# gd32foc.net
KiCad netlist of a schematic drawn in Altium Designer
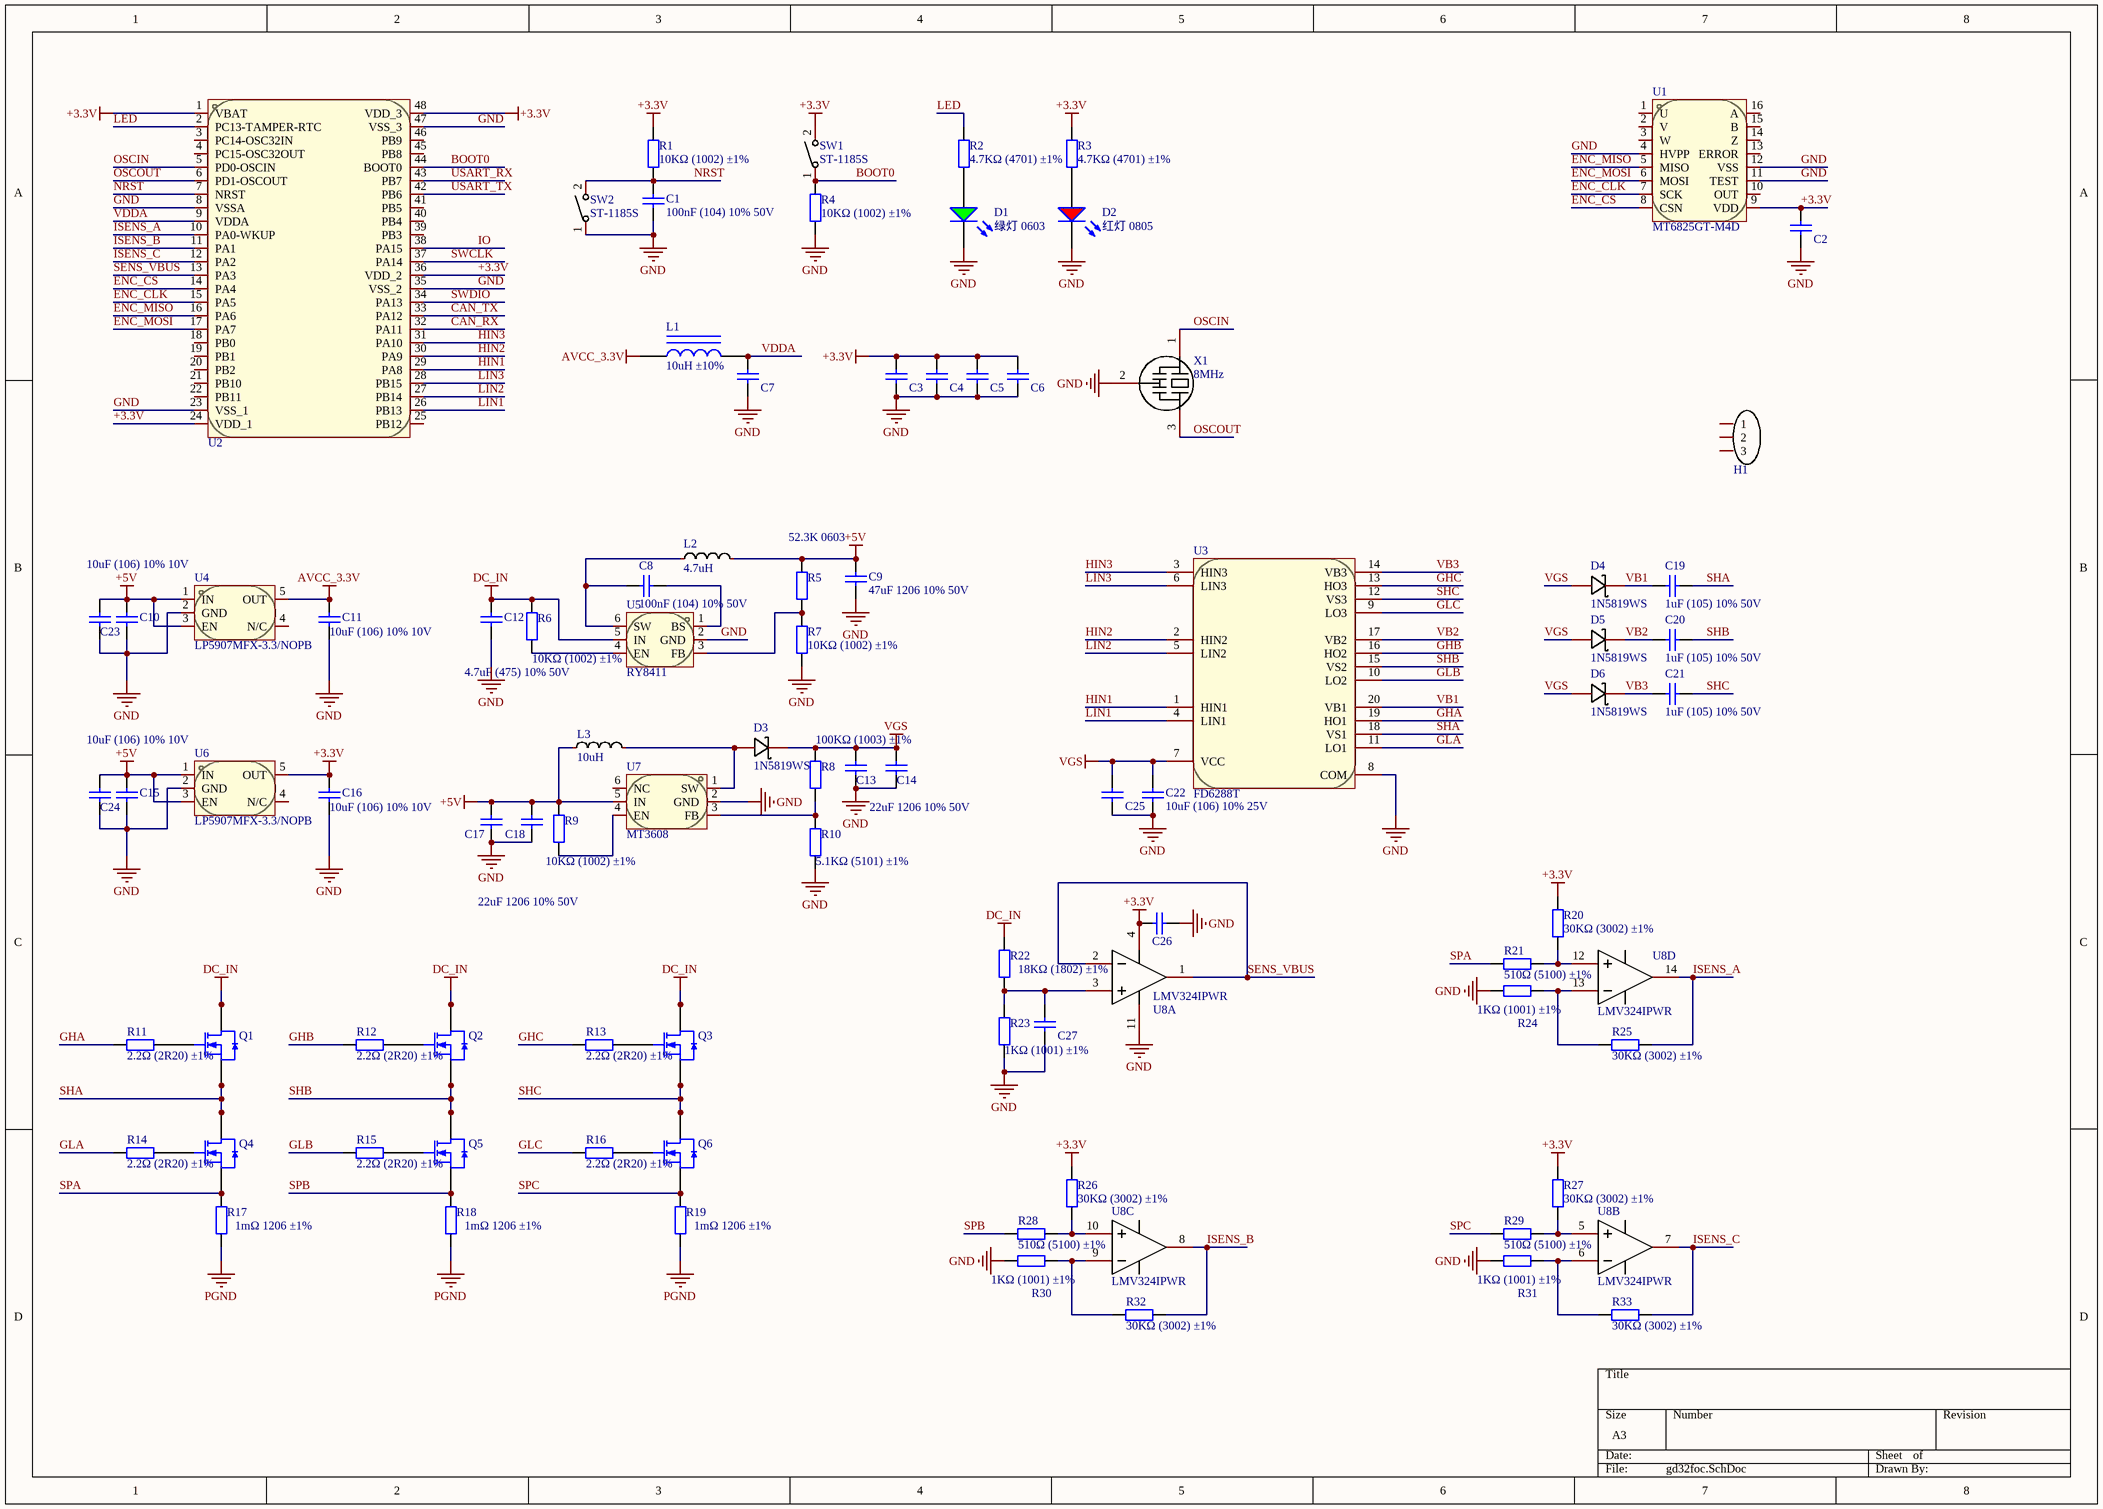
[diagram p0: gd32foc.SchDoc]

(export (version "E")
  (design (tool "Eeschema 10.0.6"))
  (components
    (comp (ref "C1")
      (value "100nF (104) 10% 50V")
      (footprint "0603_C")
      (description "贴片电容")
      (libsource (lib "Miscellaneous Devices LC") (part "0603 100nF (104) 10% 50V"))
    )
    (comp (ref "C2")
      (value "100nF (104) 10% 50V")
      (footprint "0603_C")
      (description "贴片电容")
      (libsource (lib "Miscellaneous Devices LC") (part "0603 100nF (104) 10% 50V"))
    )
    (comp (ref "C3")
      (value "100nF (104) 10% 50V")
      (footprint "0603_C")
      (description "贴片电容")
      (libsource (lib "Miscellaneous Devices LC") (part "0603 100nF (104) 10% 50V"))
    )
    (comp (ref "C4")
      (value "100nF (104) 10% 50V")
      (footprint "0603_C")
      (description "贴片电容")
      (libsource (lib "Miscellaneous Devices LC") (part "0603 100nF (104) 10% 50V"))
    )
    (comp (ref "C5")
      (value "100nF (104) 10% 50V")
      (footprint "0603_C")
      (description "贴片电容")
      (libsource (lib "Miscellaneous Devices LC") (part "0603 100nF (104) 10% 50V"))
    )
    (comp (ref "C6")
      (value "100nF (104) 10% 50V")
      (footprint "0603_C")
      (description "贴片电容")
      (libsource (lib "Miscellaneous Devices LC") (part "0603 100nF (104) 10% 50V"))
    )
    (comp (ref "C7")
      (value "100nF (104) 10% 50V")
      (footprint "0603_C")
      (description "贴片电容")
      (libsource (lib "Miscellaneous Devices LC") (part "0603 100nF (104) 10% 50V"))
    )
    (comp (ref "C8")
      (value "100nF (104) 10% 50V")
      (footprint "0603_C")
      (description "贴片电容")
      (libsource (lib "Miscellaneous Devices LC") (part "0603 100nF (104) 10% 50V"))
    )
    (comp (ref "C9")
      (value "47uF 1206 10% 50V")
      (footprint "1206_C")
      (description "贴片电容")
      (libsource (lib "Miscellaneous Devices LC") (part "1206 4.7uF (475) 10% 50V"))
    )
    (comp (ref "C10")
      (value "10uF (106) 10% 10V")
      (footprint "0603_C")
      (description "贴片电容")
      (libsource (lib "Miscellaneous Devices LC") (part "0603 10uF (106) 10% 10V"))
    )
    (comp (ref "C11")
      (value "10uF (106) 10% 10V")
      (footprint "0603_C")
      (description "贴片电容")
      (libsource (lib "Miscellaneous Devices LC") (part "0603 10uF (106) 10% 10V"))
    )
    (comp (ref "C12")
      (value "4.7uF (475) 10% 50V")
      (footprint "1206_C")
      (description "贴片电容")
      (libsource (lib "Miscellaneous Devices LC") (part "1206 4.7uF (475) 10% 50V"))
    )
    (comp (ref "C13")
      (value "22uF 1206 10% 50V")
      (footprint "1206_C")
      (description "贴片电容")
      (libsource (lib "Miscellaneous Devices LC") (part "1206 4.7uF (475) 10% 50V"))
    )
    (comp (ref "C14")
      (value "100nF (104) 10% 50V")
      (footprint "0603_C")
      (description "贴片电容")
      (libsource (lib "Miscellaneous Devices LC") (part "0603 100nF (104) 10% 50V"))
    )
    (comp (ref "C15")
      (value "10uF (106) 10% 10V")
      (footprint "0603_C")
      (description "贴片电容")
      (libsource (lib "Miscellaneous Devices LC") (part "0603 10uF (106) 10% 10V"))
    )
    (comp (ref "C16")
      (value "10uF (106) 10% 10V")
      (footprint "0603_C")
      (description "贴片电容")
      (libsource (lib "Miscellaneous Devices LC") (part "0603 10uF (106) 10% 10V"))
    )
    (comp (ref "C17")
      (value "22uF 1206 10% 50V")
      (footprint "1206_C")
      (description "贴片电容")
      (libsource (lib "Miscellaneous Devices LC") (part "1206 4.7uF (475) 10% 50V"))
    )
    (comp (ref "C18")
      (value "100nF (104) 10% 50V")
      (footprint "0603_C")
      (description "贴片电容")
      (libsource (lib "Miscellaneous Devices LC") (part "0603 100nF (104) 10% 50V"))
    )
    (comp (ref "C19")
      (value "1uF (105) 10% 50V")
      (footprint "0603_C")
      (description "贴片电容")
      (libsource (lib "Miscellaneous Devices LC") (part "0603 1uF (105) 10% 50V"))
    )
    (comp (ref "C20")
      (value "1uF (105) 10% 50V")
      (footprint "0603_C")
      (description "贴片电容")
      (libsource (lib "Miscellaneous Devices LC") (part "0603 1uF (105) 10% 50V"))
    )
    (comp (ref "C21")
      (value "1uF (105) 10% 50V")
      (footprint "0603_C")
      (description "贴片电容")
      (libsource (lib "Miscellaneous Devices LC") (part "0603 1uF (105) 10% 50V"))
    )
    (comp (ref "C22")
      (value "10uF (106) 10% 25V")
      (footprint "0805_C")
      (description "贴片电容")
      (libsource (lib "Miscellaneous Devices LC") (part "0805 10uF (106) 10% 25V"))
    )
    (comp (ref "C23")
      (value "100nF (104) 10% 50V")
      (footprint "0603_C")
      (description "贴片电容")
      (libsource (lib "Miscellaneous Devices LC") (part "0603 100nF (104) 10% 50V"))
    )
    (comp (ref "C24")
      (value "100nF (104) 10% 50V")
      (footprint "0603_C")
      (description "贴片电容")
      (libsource (lib "Miscellaneous Devices LC") (part "0603 100nF (104) 10% 50V"))
    )
    (comp (ref "C25")
      (value "100nF (104) 10% 50V")
      (footprint "0603_C")
      (description "贴片电容")
      (libsource (lib "Miscellaneous Devices LC") (part "0603 100nF (104) 10% 50V"))
    )
    (comp (ref "C26")
      (value "100nF (104) 10% 50V")
      (footprint "0603_C")
      (description "贴片电容")
      (libsource (lib "Miscellaneous Devices LC") (part "0603 100nF (104) 10% 50V"))
    )
    (comp (ref "C27")
      (value "100nF (104) 10% 50V")
      (footprint "0603_C")
      (description "贴片电容")
      (libsource (lib "Miscellaneous Devices LC") (part "0603 100nF (104) 10% 50V"))
    )
    (comp (ref "D1")
      (value "绿灯 0603")
      (footprint "0603_LED_S1")
      (description "发光二极管")
      (libsource (lib "Miscellaneous Devices LC") (part "0603 绿灯"))
    )
    (comp (ref "D2")
      (value "红灯 0805")
      (footprint "0805_LED_S1")
      (description "发光二极管")
      (libsource (lib "Miscellaneous Devices LC") (part "0805 红灯"))
    )
    (comp (ref "D3")
      (value "1N5819WS")
      (footprint "SOD-323_L1.8-W1.3-LS2.5-RD")
      (description "正向压降(Vf):600mV@1A;直流反向耐压(Vr):40V;平均整流电流(Io):1A;")
      (fields (field (name "MANUFACTURER") "Hottech(合科泰)") (field (name "NAME") "1N5819WS"))
      (libsource (lib "MyLib") (part "1N5819WS_C191023"))
    )
    (comp (ref "D4")
      (value "1N5819WS")
      (footprint "SOD-323_L1.8-W1.3-LS2.5-RD")
      (description "正向压降(Vf):600mV@1A;直流反向耐压(Vr):40V;平均整流电流(Io):1A;")
      (fields (field (name "MANUFACTURER") "Hottech(合科泰)") (field (name "NAME") "1N5819WS"))
      (libsource (lib "MyLib") (part "1N5819WS_C191023"))
    )
    (comp (ref "D5")
      (value "1N5819WS")
      (footprint "SOD-323_L1.8-W1.3-LS2.5-RD")
      (description "正向压降(Vf):600mV@1A;直流反向耐压(Vr):40V;平均整流电流(Io):1A;")
      (fields (field (name "MANUFACTURER") "Hottech(合科泰)") (field (name "NAME") "1N5819WS"))
      (libsource (lib "MyLib") (part "1N5819WS_C191023"))
    )
    (comp (ref "D6")
      (value "1N5819WS")
      (footprint "SOD-323_L1.8-W1.3-LS2.5-RD")
      (description "正向压降(Vf):600mV@1A;直流反向耐压(Vr):40V;平均整流电流(Io):1A;")
      (fields (field (name "MANUFACTURER") "Hottech(合科泰)") (field (name "NAME") "1N5819WS"))
      (libsource (lib "MyLib") (part "1N5819WS_C191023"))
    )
    (comp (ref "H1") (value "MR30-M") (footprint "MR30-M") (libsource (lib "MyLib") (part "MR30-M_卧")))
    (comp (ref "L1")
      (value "10uH ±10%")
      (footprint "0603_L")
      (description "贴片电感")
      (libsource (lib "Miscellaneous Devices LC") (part "0603 10uH 10%"))
    )
    (comp (ref "L2")
      (value "4.7uH")
      (footprint "IND-SMD_L2.5-W2.0")
      (description "电感值:4.7uH;精度:±20%;额定电流:840mA;类型:-;饱和电流(Isat):1.25A;")
      (fields
        (field (name "MANUFACTURER") "Sunlord(顺络)")
        (field (name "MANUFACTURER PART") "SWPA252012S4R7MT")
        (field (name "NAME") "4.7uH")
      )
      (libsource (lib "MyLib") (part "SWPA252012S4R7MT"))
    )
    (comp (ref "L3")
      (value "10uH")
      (footprint "IND-SMD_L2.5-W2.0_WPN252012H")
      (description "电感值:10uH;精度:±20%;额定电流:850mA;直流电阻(DCR):480mΩ;")
      (fields
        (field (name "MANUFACTURER") "Sunlord(顺络)")
        (field (name "MANUFACTURER PART") "WPN252012H100MT")
        (field (name "NAME") "10uH")
      )
      (libsource (lib "MyLib") (part "WPN252012H100MT"))
    )
    (comp (ref "Q1")
      (value "HYG025N06LS1C2")
      (footprint "DFN-8_L5.9-W5.2-P1.27-LS6.2-BL")
      (fields (field (name "MANUFACTURER") "HUAYI(华羿微)"))
      (libsource (lib "MyLib") (part "HYG025N06LS1C2"))
    )
    (comp (ref "Q2")
      (value "HYG025N06LS1C2")
      (footprint "DFN-8_L5.9-W5.2-P1.27-LS6.2-BL")
      (fields (field (name "MANUFACTURER") "HUAYI(华羿微)"))
      (libsource (lib "MyLib") (part "HYG025N06LS1C2"))
    )
    (comp (ref "Q3")
      (value "HYG025N06LS1C2")
      (footprint "DFN-8_L5.9-W5.2-P1.27-LS6.2-BL")
      (fields (field (name "MANUFACTURER") "HUAYI(华羿微)"))
      (libsource (lib "MyLib") (part "HYG025N06LS1C2"))
    )
    (comp (ref "Q4")
      (value "HYG025N06LS1C2")
      (footprint "DFN-8_L5.9-W5.2-P1.27-LS6.2-BL")
      (fields (field (name "MANUFACTURER") "HUAYI(华羿微)"))
      (libsource (lib "MyLib") (part "HYG025N06LS1C2"))
    )
    (comp (ref "Q5")
      (value "HYG025N06LS1C2")
      (footprint "DFN-8_L5.9-W5.2-P1.27-LS6.2-BL")
      (fields (field (name "MANUFACTURER") "HUAYI(华羿微)"))
      (libsource (lib "MyLib") (part "HYG025N06LS1C2"))
    )
    (comp (ref "Q6")
      (value "HYG025N06LS1C2")
      (footprint "DFN-8_L5.9-W5.2-P1.27-LS6.2-BL")
      (fields (field (name "MANUFACTURER") "HUAYI(华羿微)"))
      (libsource (lib "MyLib") (part "HYG025N06LS1C2"))
    )
    (comp (ref "R1")
      (value "10KΩ (1002) ±1%")
      (footprint "0603_R")
      (description "贴片电阻")
      (libsource (lib "Miscellaneous Devices LC") (part "0603 10KΩ (1002) 1%"))
    )
    (comp (ref "R2")
      (value "4.7KΩ (4701) ±1%")
      (footprint "0603_R")
      (description "贴片电阻")
      (libsource (lib "Miscellaneous Devices LC") (part "0603 4.7KΩ (4701) 1%"))
    )
    (comp (ref "R3")
      (value "4.7KΩ (4701) ±1%")
      (footprint "0603_R")
      (description "贴片电阻")
      (libsource (lib "Miscellaneous Devices LC") (part "0603 4.7KΩ (4701) 1%"))
    )
    (comp (ref "R4")
      (value "10KΩ (1002) ±1%")
      (footprint "0603_R")
      (description "贴片电阻")
      (libsource (lib "Miscellaneous Devices LC") (part "0603 10KΩ (1002) 1%"))
    )
    (comp (ref "R5")
      (value "52.3K 0603")
      (footprint "0603_R")
      (description "贴片电阻")
      (libsource (lib "Miscellaneous Devices LC") (part "0603 100KΩ (1003) 1%"))
    )
    (comp (ref "R6")
      (value "10KΩ (1002) ±1%")
      (footprint "0603_R")
      (description "贴片电阻")
      (libsource (lib "Miscellaneous Devices LC") (part "0603 10KΩ (1002) 1%"))
    )
    (comp (ref "R7")
      (value "10KΩ (1002) ±1%")
      (footprint "0603_R")
      (description "贴片电阻")
      (libsource (lib "Miscellaneous Devices LC") (part "0603 10KΩ (1002) 1%"))
    )
    (comp (ref "R8")
      (value "100KΩ (1003) ±1%")
      (footprint "0603_R")
      (description "贴片电阻")
      (libsource (lib "Miscellaneous Devices LC") (part "0603 100KΩ (1003) 1%"))
    )
    (comp (ref "R9")
      (value "10KΩ (1002) ±1%")
      (footprint "0603_R")
      (description "贴片电阻")
      (libsource (lib "Miscellaneous Devices LC") (part "0603 10KΩ (1002) 1%"))
    )
    (comp (ref "R10")
      (value "5.1KΩ (5101) ±1%")
      (footprint "0603_R")
      (description "贴片电阻")
      (libsource (lib "Miscellaneous Devices LC") (part "0603 5.1KΩ (5101) 1%"))
    )
    (comp (ref "R11")
      (value "2.2Ω (2R20) ±1%")
      (footprint "0603_R")
      (description "贴片电阻")
      (libsource (lib "Miscellaneous Devices LC") (part "0603 2.2Ω (2R20) 1%"))
    )
    (comp (ref "R12")
      (value "2.2Ω (2R20) ±1%")
      (footprint "0603_R")
      (description "贴片电阻")
      (libsource (lib "Miscellaneous Devices LC") (part "0603 2.2Ω (2R20) 1%"))
    )
    (comp (ref "R13")
      (value "2.2Ω (2R20) ±1%")
      (footprint "0603_R")
      (description "贴片电阻")
      (libsource (lib "Miscellaneous Devices LC") (part "0603 2.2Ω (2R20) 1%"))
    )
    (comp (ref "R14")
      (value "2.2Ω (2R20) ±1%")
      (footprint "0603_R")
      (description "贴片电阻")
      (libsource (lib "Miscellaneous Devices LC") (part "0603 2.2Ω (2R20) 1%"))
    )
    (comp (ref "R15")
      (value "2.2Ω (2R20) ±1%")
      (footprint "0603_R")
      (description "贴片电阻")
      (libsource (lib "Miscellaneous Devices LC") (part "0603 2.2Ω (2R20) 1%"))
    )
    (comp (ref "R16")
      (value "2.2Ω (2R20) ±1%")
      (footprint "0603_R")
      (description "贴片电阻")
      (libsource (lib "Miscellaneous Devices LC") (part "0603 2.2Ω (2R20) 1%"))
    )
    (comp (ref "R17")
      (value "1mΩ 1206 ±1%")
      (footprint "1206_R")
      (description "贴片电阻")
      (libsource (lib "Miscellaneous Devices LC") (part "1206 0.1Ω (R100) 1%"))
    )
    (comp (ref "R18")
      (value "1mΩ 1206 ±1%")
      (footprint "1206_R")
      (description "贴片电阻")
      (libsource (lib "Miscellaneous Devices LC") (part "1206 0.1Ω (R100) 1%"))
    )
    (comp (ref "R19")
      (value "1mΩ 1206 ±1%")
      (footprint "1206_R")
      (description "贴片电阻")
      (libsource (lib "Miscellaneous Devices LC") (part "1206 0.1Ω (R100) 1%"))
    )
    (comp (ref "R20")
      (value "30KΩ (3002) ±1%")
      (footprint "0603_R")
      (description "贴片电阻")
      (libsource (lib "") (part "0603 30KΩ (3002) 1%_1"))
    )
    (comp (ref "R21")
      (value "510Ω (5100) ±1%")
      (footprint "0603_R")
      (description "贴片电阻")
      (libsource (lib "Miscellaneous Devices LC") (part "0603 510Ω (5100) 1%"))
    )
    (comp (ref "R22")
      (value "18KΩ (1802) ±1%")
      (footprint "0603_R")
      (description "贴片电阻")
      (libsource (lib "Miscellaneous Devices LC") (part "0603 18KΩ (1802) 1%"))
    )
    (comp (ref "R23")
      (value "1KΩ (1001) ±1%")
      (footprint "0603_R")
      (description "贴片电阻")
      (libsource (lib "") (part "0603 1KΩ (1001) 1%_1"))
    )
    (comp (ref "R24")
      (value "1KΩ (1001) ±1%")
      (footprint "0603_R")
      (description "贴片电阻")
      (libsource (lib "Miscellaneous Devices LC") (part "0603 1KΩ (1001) 1%"))
    )
    (comp (ref "R25")
      (value "30KΩ (3002) ±1%")
      (footprint "0603_R")
      (description "贴片电阻")
      (libsource (lib "Miscellaneous Devices LC") (part "0603 30KΩ (3002) 1%"))
    )
    (comp (ref "R26")
      (value "30KΩ (3002) ±1%")
      (footprint "0603_R")
      (description "贴片电阻")
      (libsource (lib "") (part "0603 30KΩ (3002) 1%_1"))
    )
    (comp (ref "R27")
      (value "30KΩ (3002) ±1%")
      (footprint "0603_R")
      (description "贴片电阻")
      (libsource (lib "") (part "0603 30KΩ (3002) 1%_1"))
    )
    (comp (ref "R28")
      (value "510Ω (5100) ±1%")
      (footprint "0603_R")
      (description "贴片电阻")
      (libsource (lib "Miscellaneous Devices LC") (part "0603 510Ω (5100) 1%"))
    )
    (comp (ref "R29")
      (value "510Ω (5100) ±1%")
      (footprint "0603_R")
      (description "贴片电阻")
      (libsource (lib "Miscellaneous Devices LC") (part "0603 510Ω (5100) 1%"))
    )
    (comp (ref "R30")
      (value "1KΩ (1001) ±1%")
      (footprint "0603_R")
      (description "贴片电阻")
      (libsource (lib "Miscellaneous Devices LC") (part "0603 1KΩ (1001) 1%"))
    )
    (comp (ref "R31")
      (value "1KΩ (1001) ±1%")
      (footprint "0603_R")
      (description "贴片电阻")
      (libsource (lib "Miscellaneous Devices LC") (part "0603 1KΩ (1001) 1%"))
    )
    (comp (ref "R32")
      (value "30KΩ (3002) ±1%")
      (footprint "0603_R")
      (description "贴片电阻")
      (libsource (lib "Miscellaneous Devices LC") (part "0603 30KΩ (3002) 1%"))
    )
    (comp (ref "R33")
      (value "30KΩ (3002) ±1%")
      (footprint "0603_R")
      (description "贴片电阻")
      (libsource (lib "Miscellaneous Devices LC") (part "0603 30KΩ (3002) 1%"))
    )
    (comp (ref "SW1")
      (value "ST-1185S")
      (footprint "SW-SMD_ST-1185S")
      (description "电路结构:单刀单掷;带支架:否;触点电流:50mA;额定电压(DC):12V;安装方式:立贴;绝缘电阻:100MΩ;机械寿命:10万次;")
      (fields (field (name "MANUFACTURER") "RISHENG(日昇)") (field (name "NAME") "ST-1185S"))
      (libsource (lib "MyLib") (part "ST-1185S"))
    )
    (comp (ref "SW2")
      (value "ST-1185S")
      (footprint "SW-SMD_ST-1185S")
      (description "电路结构:单刀单掷;带支架:否;触点电流:50mA;额定电压(DC):12V;安装方式:立贴;绝缘电阻:100MΩ;机械寿命:10万次;")
      (fields (field (name "MANUFACTURER") "RISHENG(日昇)") (field (name "NAME") "ST-1185S"))
      (libsource (lib "MyLib") (part "ST-1185S"))
    )
    (comp (ref "U1")
      (value "MT6825GT-M4D")
      (footprint "TSSOP-16_L5.0-W4.4-P0.65-LS6.4-BL")
      (description "AB=2500线，Z=4LSB, UVW=4对极, PWM=1KHz，四线SPI")
      (fields (field (name "MANUFACTURER") "MagnTek(麦歌恩)") (field (name "NAME") "MT6825GT-M4D"))
      (libsource (lib "MyLib") (part "MT6825GT-M4D"))
    )
    (comp (ref "U2")
      (value "GD32C103CBT6")
      (footprint "LQFP-48_L7.0-W7.0-P0.50-LS9.0-BL")
      (description "CPU内核:ARM Cortex-M4;CPU最大主频:120MHz;程序存储容量:128KB;程序存储器类型:FLASH;GPIO端口数量:37;工作电压范围:-;RAM总容量:32KB;")
      (fields (field (name "MANUFACTURER") "GigaDevice(兆易创新)"))
      (libsource (lib "MyLib") (part "GD32C103CBT6"))
    )
    (comp (ref "U3")
      (value "FD6288T")
      (footprint "TSSOP-20_L6.5-W4.4-P0.65-LS6.4-BL")
      (description "三个独立的半桥栅极驱动集成电路芯片")
      (fields (field (name "MANUFACTURER") "Fortior Tech(峰岹)") (field (name "NAME") "FD6288T"))
      (libsource (lib "MyLib") (part "FD6288T"))
    )
    (comp (ref "U4")
      (value "LP5907MFX-3.3/NOPB")
      (footprint "SOT-23-5_L3.0-W1.7-P0.95-LS2.8-BR")
      (description "输出类型:固定;输出极性:正;最大输入电压:5.5V;输出电压:3.3V;输出电流:250mA;电源纹波抑制比(PSRR):90dB;")
      (fields (field (name "MANUFACTURER") "TI(德州仪器)") (field (name "NAME") "LP5907MFX-3.3/NOPB"))
      (libsource (lib "MyLib") (part "LP5907MFX-3.3/NOPB"))
    )
    (comp (ref "U5")
      (value "RY8411")
      (footprint "SOT-23-6_L2.9-W1.6-P0.95-LS2.8-TL")
      (fields (field (name "MANUFACTURER") "RYCHiP(蕊源)") (field (name "NAME") "RY8411"))
      (libsource (lib "MyLib") (part "RY8411_C2935411"))
    )
    (comp (ref "U6")
      (value "LP5907MFX-3.3/NOPB")
      (footprint "SOT-23-5_L3.0-W1.7-P0.95-LS2.8-BR")
      (description "输出类型:固定;输出极性:正;最大输入电压:5.5V;输出电压:3.3V;输出电流:250mA;电源纹波抑制比(PSRR):90dB;")
      (fields (field (name "MANUFACTURER") "TI(德州仪器)") (field (name "NAME") "LP5907MFX-3.3/NOPB"))
      (libsource (lib "MyLib") (part "LP5907MFX-3.3/NOPB"))
    )
    (comp (ref "U7")
      (value "MT3608")
      (footprint "SOT-23-6_L2.9-W1.6-P0.95-LS2.8-BL")
      (description "功能类型:升压型;输入电压:2V~24V;输出电压:28V;输出电流(最大值):-;")
      (fields (field (name "MANUFACTURER") "西安航天民芯") (field (name "NAME") "MT3608"))
      (libsource (lib "MyLib") (part "MT3608"))
    )
    (comp (ref "U8")
      (value "LMV324IPWR")
      (footprint "TSSOP-14_L5.0-W4.4-P0.65-LS6.4-BL")
      (description "放大器组数:-;")
      (fields (field (name "MANUFACTURER") "TI(德州仪器)") (field (name "NAME") "LMV324IPWR"))
      (libsource (lib "MyLib") (part "LMV324IPWR"))
    )
    (comp (ref "X1")
      (value "8MHz")
      (footprint "OSC-SMD_3P-L3.2-W1.3-P1.2-L")
      (description "频率:8MHz;频率公差:±0.5%;内置负载电容:33pF;谐振阻抗:-;")
      (fields
        (field (name "MANUFACTURER") "muRata(村田)")
        (field (name "MANUFACTURER PART") "CSTCE8M00G55-R0")
        (field (name "NAME") "8MHz")
      )
      (libsource (lib "MyLib") (part "CSTCE8M00G55-R0"))
    )
  )
  (nets
    (net (code "1") (name "+3.3V") (class "Default")
      (node (ref "C16") (pin "2") (pinfunction "2_2") (pintype "passive"))
      (node (ref "C2") (pin "2") (pinfunction "2_2") (pintype "passive"))
      (node (ref "C26") (pin "2") (pinfunction "2_2") (pintype "passive"))
      (node (ref "C3") (pin "2") (pinfunction "2_2") (pintype "passive"))
      (node (ref "C4") (pin "2") (pinfunction "2_2") (pintype "passive"))
      (node (ref "C5") (pin "2") (pinfunction "2_2") (pintype "passive"))
      (node (ref "C6") (pin "2") (pinfunction "2_2") (pintype "passive"))
      (node (ref "R1") (pin "2") (pinfunction "2_2") (pintype "passive"))
      (node (ref "R20") (pin "2") (pinfunction "2_2") (pintype "passive"))
      (node (ref "R26") (pin "2") (pinfunction "2_2") (pintype "passive"))
      (node (ref "R27") (pin "2") (pinfunction "2_2") (pintype "passive"))
      (node (ref "R3") (pin "2") (pinfunction "2_2") (pintype "passive"))
      (node (ref "SW1") (pin "2") (pinfunction "2_2") (pintype "passive"))
      (node (ref "U1") (pin "9") (pinfunction "VDD_9") (pintype "passive"))
      (node (ref "U2") (pin "1") (pinfunction "VBAT_1") (pintype "passive"))
      (node (ref "U2") (pin "24") (pinfunction "VDD_1_24") (pintype "passive"))
      (node (ref "U2") (pin "36") (pinfunction "VDD_2_36") (pintype "passive"))
      (node (ref "U2") (pin "48") (pinfunction "VDD_3_48") (pintype "passive"))
      (node (ref "U6") (pin "5") (pinfunction "OUT_5") (pintype "passive"))
      (node (ref "U8") (pin "4") (pinfunction "VCC+_4") (pintype "passive"))
    )
    (net (code "2") (name "+5V") (class "Default")
      (node (ref "C10") (pin "2") (pinfunction "2_2") (pintype "passive"))
      (node (ref "C15") (pin "2") (pinfunction "2_2") (pintype "passive"))
      (node (ref "C17") (pin "2") (pinfunction "2_2") (pintype "passive"))
      (node (ref "C18") (pin "2") (pinfunction "2_2") (pintype "passive"))
      (node (ref "C23") (pin "2") (pinfunction "2_2") (pintype "passive"))
      (node (ref "C24") (pin "2") (pinfunction "2_2") (pintype "passive"))
      (node (ref "C9") (pin "2") (pinfunction "2_2") (pintype "passive"))
      (node (ref "L2") (pin "2") (pinfunction "2_2") (pintype "passive"))
      (node (ref "L3") (pin "1") (pinfunction "1_1") (pintype "passive"))
      (node (ref "R5") (pin "2") (pinfunction "2_2") (pintype "passive"))
      (node (ref "R9") (pin "2") (pinfunction "2_2") (pintype "passive"))
      (node (ref "U4") (pin "1") (pinfunction "IN_1") (pintype "passive"))
      (node (ref "U4") (pin "3") (pinfunction "EN_3") (pintype "passive"))
      (node (ref "U6") (pin "1") (pinfunction "IN_1") (pintype "passive"))
      (node (ref "U6") (pin "3") (pinfunction "EN_3") (pintype "passive"))
      (node (ref "U7") (pin "5") (pinfunction "IN_5") (pintype "passive"))
    )
    (net (code "3") (name "/BOOT0") (class "Default")
      (node (ref "R4") (pin "2") (pinfunction "2_2") (pintype "passive"))
      (node (ref "SW1") (pin "1") (pinfunction "1_1") (pintype "passive"))
      (node (ref "U2") (pin "44") (pinfunction "BOOT0_44") (pintype "passive"))
    )
    (net (code "4") (name "/CAN_RX") (class "Default")
      (node (ref "U2") (pin "32") (pinfunction "PA11_32") (pintype "passive"))
    )
    (net (code "5") (name "/CAN_TX") (class "Default")
      (node (ref "U2") (pin "33") (pinfunction "PA12_33") (pintype "passive"))
    )
    (net (code "6") (name "/ENC_CLK") (class "Default")
      (node (ref "U1") (pin "7") (pinfunction "SCK_7") (pintype "passive"))
      (node (ref "U2") (pin "15") (pinfunction "PA5_15") (pintype "passive"))
    )
    (net (code "7") (name "/ENC_CS") (class "Default")
      (node (ref "U1") (pin "8") (pinfunction "CSN_8") (pintype "passive"))
      (node (ref "U2") (pin "14") (pinfunction "PA4_14") (pintype "passive"))
    )
    (net (code "8") (name "/ENC_MISO") (class "Default")
      (node (ref "U1") (pin "5") (pinfunction "MISO_5") (pintype "passive"))
      (node (ref "U2") (pin "16") (pinfunction "PA6_16") (pintype "passive"))
    )
    (net (code "9") (name "/ENC_MOSI") (class "Default")
      (node (ref "U1") (pin "6") (pinfunction "MOSI_6") (pintype "passive"))
      (node (ref "U2") (pin "17") (pinfunction "PA7_17") (pintype "passive"))
    )
    (net (code "10") (name "/GHA") (class "Default")
      (node (ref "R11") (pin "1") (pinfunction "1_1") (pintype "passive"))
      (node (ref "U3") (pin "19") (pinfunction "HO1_19") (pintype "passive"))
    )
    (net (code "11") (name "/GHB") (class "Default")
      (node (ref "R12") (pin "1") (pinfunction "1_1") (pintype "passive"))
      (node (ref "U3") (pin "16") (pinfunction "HO2_16") (pintype "passive"))
    )
    (net (code "12") (name "/GHC") (class "Default")
      (node (ref "R13") (pin "1") (pinfunction "1_1") (pintype "passive"))
      (node (ref "U3") (pin "13") (pinfunction "HO3_13") (pintype "passive"))
    )
    (net (code "13") (name "/GLA") (class "Default")
      (node (ref "R14") (pin "1") (pinfunction "1_1") (pintype "passive"))
      (node (ref "U3") (pin "11") (pinfunction "LO1_11") (pintype "passive"))
    )
    (net (code "14") (name "/GLB") (class "Default")
      (node (ref "R15") (pin "1") (pinfunction "1_1") (pintype "passive"))
      (node (ref "U3") (pin "10") (pinfunction "LO2_10") (pintype "passive"))
    )
    (net (code "15") (name "/GLC") (class "Default")
      (node (ref "R16") (pin "1") (pinfunction "1_1") (pintype "passive"))
      (node (ref "U3") (pin "9") (pinfunction "LO3_9") (pintype "passive"))
    )
    (net (code "16") (name "/HIN1") (class "Default")
      (node (ref "U2") (pin "29") (pinfunction "PA8_29") (pintype "passive"))
      (node (ref "U3") (pin "1") (pinfunction "HIN1_1") (pintype "passive"))
    )
    (net (code "17") (name "/HIN2") (class "Default")
      (node (ref "U2") (pin "30") (pinfunction "PA9_30") (pintype "passive"))
      (node (ref "U3") (pin "2") (pinfunction "HIN2_2") (pintype "passive"))
    )
    (net (code "18") (name "/HIN3") (class "Default")
      (node (ref "U2") (pin "31") (pinfunction "PA10_31") (pintype "passive"))
      (node (ref "U3") (pin "3") (pinfunction "HIN3_3") (pintype "passive"))
    )
    (net (code "19") (name "/IO") (class "Default")
      (node (ref "U2") (pin "38") (pinfunction "PA15_38") (pintype "passive"))
    )
    (net (code "20") (name "/ISENS_A") (class "Default")
      (node (ref "R25") (pin "1") (pinfunction "1_1") (pintype "passive"))
      (node (ref "U2") (pin "10") (pinfunction "PA0-WKUP_10") (pintype "passive"))
      (node (ref "U8") (pin "14") (pinfunction "OUT4_14") (pintype "passive"))
    )
    (net (code "21") (name "/ISENS_B") (class "Default")
      (node (ref "R32") (pin "1") (pinfunction "1_1") (pintype "passive"))
      (node (ref "U2") (pin "11") (pinfunction "PA1_11") (pintype "passive"))
      (node (ref "U8") (pin "8") (pinfunction "OUT3_8") (pintype "passive"))
    )
    (net (code "22") (name "/ISENS_C") (class "Default")
      (node (ref "R33") (pin "1") (pinfunction "1_1") (pintype "passive"))
      (node (ref "U2") (pin "12") (pinfunction "PA2_12") (pintype "passive"))
      (node (ref "U8") (pin "7") (pinfunction "OUT2_7") (pintype "passive"))
    )
    (net (code "23") (name "/LED") (class "Default")
      (node (ref "R2") (pin "2") (pinfunction "2_2") (pintype "passive"))
      (node (ref "U2") (pin "2") (pinfunction "PC13-TAMPER-RTC_2") (pintype "passive"))
    )
    (net (code "24") (name "/LIN1") (class "Default")
      (node (ref "U2") (pin "26") (pinfunction "PB13_26") (pintype "passive"))
      (node (ref "U3") (pin "4") (pinfunction "LIN1_4") (pintype "passive"))
    )
    (net (code "25") (name "/LIN2") (class "Default")
      (node (ref "U2") (pin "27") (pinfunction "PB14_27") (pintype "passive"))
      (node (ref "U3") (pin "5") (pinfunction "LIN2_5") (pintype "passive"))
    )
    (net (code "26") (name "/LIN3") (class "Default")
      (node (ref "U2") (pin "28") (pinfunction "PB15_28") (pintype "passive"))
      (node (ref "U3") (pin "6") (pinfunction "LIN3_6") (pintype "passive"))
    )
    (net (code "27") (name "/NRST") (class "Default")
      (node (ref "C1") (pin "2") (pinfunction "2_2") (pintype "passive"))
      (node (ref "R1") (pin "1") (pinfunction "1_1") (pintype "passive"))
      (node (ref "SW2") (pin "2") (pinfunction "2_2") (pintype "passive"))
      (node (ref "U2") (pin "7") (pinfunction "NRST_7") (pintype "passive"))
    )
    (net (code "28") (name "/OSCIN") (class "Default")
      (node (ref "U2") (pin "5") (pinfunction "PD0-OSCIN_5") (pintype "passive"))
      (node (ref "X1") (pin "1") (pinfunction "1_1") (pintype "passive"))
    )
    (net (code "29") (name "/OSCOUT") (class "Default")
      (node (ref "U2") (pin "6") (pinfunction "PD1-OSCOUT_6") (pintype "passive"))
      (node (ref "X1") (pin "3") (pinfunction "3_3") (pintype "passive"))
    )
    (net (code "30") (name "/SENS_VBUS") (class "Default")
      (node (ref "U2") (pin "13") (pinfunction "PA3_13") (pintype "passive"))
      (node (ref "U8") (pin "1") (pinfunction "OUT1_1") (pintype "passive"))
      (node (ref "U8") (pin "2") (pinfunction "IN1-_2") (pintype "passive"))
    )
    (net (code "31") (name "/SHA") (class "Default")
      (node (ref "C19") (pin "2") (pinfunction "2_2") (pintype "passive"))
      (node (ref "Q1") (pin "1") (pinfunction "S_1") (pintype "passive"))
      (node (ref "Q1") (pin "2") (pinfunction "S_2") (pintype "passive"))
      (node (ref "Q1") (pin "3") (pinfunction "S_3") (pintype "passive"))
      (node (ref "Q4") (pin "5") (pinfunction "D_5") (pintype "passive"))
      (node (ref "Q4") (pin "6") (pinfunction "D_6") (pintype "passive"))
      (node (ref "Q4") (pin "7") (pinfunction "D_7") (pintype "passive"))
      (node (ref "Q4") (pin "8") (pinfunction "D_8") (pintype "passive"))
      (node (ref "Q4") (pin "9") (pinfunction "D_9") (pintype "passive"))
      (node (ref "U3") (pin "18") (pinfunction "VS1_18") (pintype "passive"))
    )
    (net (code "32") (name "/SHB") (class "Default")
      (node (ref "C20") (pin "2") (pinfunction "2_2") (pintype "passive"))
      (node (ref "Q2") (pin "1") (pinfunction "S_1") (pintype "passive"))
      (node (ref "Q2") (pin "2") (pinfunction "S_2") (pintype "passive"))
      (node (ref "Q2") (pin "3") (pinfunction "S_3") (pintype "passive"))
      (node (ref "Q5") (pin "5") (pinfunction "D_5") (pintype "passive"))
      (node (ref "Q5") (pin "6") (pinfunction "D_6") (pintype "passive"))
      (node (ref "Q5") (pin "7") (pinfunction "D_7") (pintype "passive"))
      (node (ref "Q5") (pin "8") (pinfunction "D_8") (pintype "passive"))
      (node (ref "Q5") (pin "9") (pinfunction "D_9") (pintype "passive"))
      (node (ref "U3") (pin "15") (pinfunction "VS2_15") (pintype "passive"))
    )
    (net (code "33") (name "/SHC") (class "Default")
      (node (ref "C21") (pin "2") (pinfunction "2_2") (pintype "passive"))
      (node (ref "Q3") (pin "1") (pinfunction "S_1") (pintype "passive"))
      (node (ref "Q3") (pin "2") (pinfunction "S_2") (pintype "passive"))
      (node (ref "Q3") (pin "3") (pinfunction "S_3") (pintype "passive"))
      (node (ref "Q6") (pin "5") (pinfunction "D_5") (pintype "passive"))
      (node (ref "Q6") (pin "6") (pinfunction "D_6") (pintype "passive"))
      (node (ref "Q6") (pin "7") (pinfunction "D_7") (pintype "passive"))
      (node (ref "Q6") (pin "8") (pinfunction "D_8") (pintype "passive"))
      (node (ref "Q6") (pin "9") (pinfunction "D_9") (pintype "passive"))
      (node (ref "U3") (pin "12") (pinfunction "VS3_12") (pintype "passive"))
    )
    (net (code "34") (name "/SPA") (class "Default")
      (node (ref "Q4") (pin "1") (pinfunction "S_1") (pintype "passive"))
      (node (ref "Q4") (pin "2") (pinfunction "S_2") (pintype "passive"))
      (node (ref "Q4") (pin "3") (pinfunction "S_3") (pintype "passive"))
      (node (ref "R17") (pin "2") (pinfunction "2_2") (pintype "passive"))
      (node (ref "R21") (pin "1") (pinfunction "1_1") (pintype "passive"))
    )
    (net (code "35") (name "/SPB") (class "Default")
      (node (ref "Q5") (pin "1") (pinfunction "S_1") (pintype "passive"))
      (node (ref "Q5") (pin "2") (pinfunction "S_2") (pintype "passive"))
      (node (ref "Q5") (pin "3") (pinfunction "S_3") (pintype "passive"))
      (node (ref "R18") (pin "2") (pinfunction "2_2") (pintype "passive"))
      (node (ref "R28") (pin "1") (pinfunction "1_1") (pintype "passive"))
    )
    (net (code "36") (name "/SPC") (class "Default")
      (node (ref "Q6") (pin "1") (pinfunction "S_1") (pintype "passive"))
      (node (ref "Q6") (pin "2") (pinfunction "S_2") (pintype "passive"))
      (node (ref "Q6") (pin "3") (pinfunction "S_3") (pintype "passive"))
      (node (ref "R19") (pin "2") (pinfunction "2_2") (pintype "passive"))
      (node (ref "R29") (pin "1") (pinfunction "1_1") (pintype "passive"))
    )
    (net (code "37") (name "/SWCLK") (class "Default")
      (node (ref "U2") (pin "37") (pinfunction "PA14_37") (pintype "passive"))
    )
    (net (code "38") (name "/SWDIO") (class "Default")
      (node (ref "U2") (pin "34") (pinfunction "PA13_34") (pintype "passive"))
    )
    (net (code "39") (name "/USART_RX") (class "Default")
      (node (ref "U2") (pin "43") (pinfunction "PB7_43") (pintype "passive"))
    )
    (net (code "40") (name "/USART_TX") (class "Default")
      (node (ref "U2") (pin "42") (pinfunction "PB6_42") (pintype "passive"))
    )
    (net (code "41") (name "/VB1") (class "Default")
      (node (ref "C19") (pin "1") (pinfunction "1_1") (pintype "passive"))
      (node (ref "D4") (pin "1") (pinfunction "K_1") (pintype "passive"))
      (node (ref "U3") (pin "20") (pinfunction "VB1_20") (pintype "passive"))
    )
    (net (code "42") (name "/VB2") (class "Default")
      (node (ref "C20") (pin "1") (pinfunction "1_1") (pintype "passive"))
      (node (ref "D5") (pin "1") (pinfunction "K_1") (pintype "passive"))
      (node (ref "U3") (pin "17") (pinfunction "VB2_17") (pintype "passive"))
    )
    (net (code "43") (name "/VB3") (class "Default")
      (node (ref "C21") (pin "1") (pinfunction "1_1") (pintype "passive"))
      (node (ref "D6") (pin "1") (pinfunction "K_1") (pintype "passive"))
      (node (ref "U3") (pin "14") (pinfunction "VB3_14") (pintype "passive"))
    )
    (net (code "44") (name "/VDDA") (class "Default")
      (node (ref "C7") (pin "2") (pinfunction "2_2") (pintype "passive"))
      (node (ref "L1") (pin "2") (pinfunction "2_2") (pintype "passive"))
      (node (ref "U2") (pin "9") (pinfunction "VDDA_9") (pintype "passive"))
    )
    (net (code "45") (name "AVCC_3.3V") (class "Default")
      (node (ref "C11") (pin "2") (pinfunction "2_2") (pintype "passive"))
      (node (ref "L1") (pin "1") (pinfunction "1_1") (pintype "passive"))
      (node (ref "U4") (pin "5") (pinfunction "OUT_5") (pintype "passive"))
    )
    (net (code "46") (name "DC_IN") (class "Default")
      (node (ref "C12") (pin "2") (pinfunction "2_2") (pintype "passive"))
      (node (ref "Q1") (pin "5") (pinfunction "D_5") (pintype "passive"))
      (node (ref "Q1") (pin "6") (pinfunction "D_6") (pintype "passive"))
      (node (ref "Q1") (pin "7") (pinfunction "D_7") (pintype "passive"))
      (node (ref "Q1") (pin "8") (pinfunction "D_8") (pintype "passive"))
      (node (ref "Q1") (pin "9") (pinfunction "D_9") (pintype "passive"))
      (node (ref "Q2") (pin "5") (pinfunction "D_5") (pintype "passive"))
      (node (ref "Q2") (pin "6") (pinfunction "D_6") (pintype "passive"))
      (node (ref "Q2") (pin "7") (pinfunction "D_7") (pintype "passive"))
      (node (ref "Q2") (pin "8") (pinfunction "D_8") (pintype "passive"))
      (node (ref "Q2") (pin "9") (pinfunction "D_9") (pintype "passive"))
      (node (ref "Q3") (pin "5") (pinfunction "D_5") (pintype "passive"))
      (node (ref "Q3") (pin "6") (pinfunction "D_6") (pintype "passive"))
      (node (ref "Q3") (pin "7") (pinfunction "D_7") (pintype "passive"))
      (node (ref "Q3") (pin "8") (pinfunction "D_8") (pintype "passive"))
      (node (ref "Q3") (pin "9") (pinfunction "D_9") (pintype "passive"))
      (node (ref "R22") (pin "2") (pinfunction "2_2") (pintype "passive"))
      (node (ref "R6") (pin "2") (pinfunction "2_2") (pintype "passive"))
      (node (ref "U5") (pin "5") (pinfunction "IN_5") (pintype "passive"))
    )
    (net (code "47") (name "GND") (class "Default")
      (node (ref "C1") (pin "1") (pinfunction "1_1") (pintype "passive"))
      (node (ref "C10") (pin "1") (pinfunction "1_1") (pintype "passive"))
      (node (ref "C11") (pin "1") (pinfunction "1_1") (pintype "passive"))
      (node (ref "C12") (pin "1") (pinfunction "1_1") (pintype "passive"))
      (node (ref "C13") (pin "1") (pinfunction "1_1") (pintype "passive"))
      (node (ref "C14") (pin "1") (pinfunction "1_1") (pintype "passive"))
      (node (ref "C15") (pin "1") (pinfunction "1_1") (pintype "passive"))
      (node (ref "C16") (pin "1") (pinfunction "1_1") (pintype "passive"))
      (node (ref "C17") (pin "1") (pinfunction "1_1") (pintype "passive"))
      (node (ref "C18") (pin "1") (pinfunction "1_1") (pintype "passive"))
      (node (ref "C2") (pin "1") (pinfunction "1_1") (pintype "passive"))
      (node (ref "C22") (pin "1") (pinfunction "1_1") (pintype "passive"))
      (node (ref "C23") (pin "1") (pinfunction "1_1") (pintype "passive"))
      (node (ref "C24") (pin "1") (pinfunction "1_1") (pintype "passive"))
      (node (ref "C25") (pin "1") (pinfunction "1_1") (pintype "passive"))
      (node (ref "C26") (pin "1") (pinfunction "1_1") (pintype "passive"))
      (node (ref "C27") (pin "1") (pinfunction "1_1") (pintype "passive"))
      (node (ref "C3") (pin "1") (pinfunction "1_1") (pintype "passive"))
      (node (ref "C4") (pin "1") (pinfunction "1_1") (pintype "passive"))
      (node (ref "C5") (pin "1") (pinfunction "1_1") (pintype "passive"))
      (node (ref "C6") (pin "1") (pinfunction "1_1") (pintype "passive"))
      (node (ref "C7") (pin "1") (pinfunction "1_1") (pintype "passive"))
      (node (ref "C9") (pin "1") (pinfunction "1_1") (pintype "passive"))
      (node (ref "D1") (pin "K") (pinfunction "K_K") (pintype "passive"))
      (node (ref "D2") (pin "K") (pinfunction "K_K") (pintype "passive"))
      (node (ref "R10") (pin "1") (pinfunction "1_1") (pintype "passive"))
      (node (ref "R23") (pin "1") (pinfunction "1_1") (pintype "passive"))
      (node (ref "R24") (pin "1") (pinfunction "1_1") (pintype "passive"))
      (node (ref "R30") (pin "1") (pinfunction "1_1") (pintype "passive"))
      (node (ref "R31") (pin "1") (pinfunction "1_1") (pintype "passive"))
      (node (ref "R4") (pin "1") (pinfunction "1_1") (pintype "passive"))
      (node (ref "R7") (pin "1") (pinfunction "1_1") (pintype "passive"))
      (node (ref "SW2") (pin "1") (pinfunction "1_1") (pintype "passive"))
      (node (ref "U1") (pin "11") (pinfunction "TEST_11") (pintype "passive"))
      (node (ref "U1") (pin "12") (pinfunction "VSS_12") (pintype "passive"))
      (node (ref "U1") (pin "4") (pinfunction "HVPP_4") (pintype "passive"))
      (node (ref "U2") (pin "23") (pinfunction "VSS_1_23") (pintype "passive"))
      (node (ref "U2") (pin "35") (pinfunction "VSS_2_35") (pintype "passive"))
      (node (ref "U2") (pin "47") (pinfunction "VSS_3_47") (pintype "passive"))
      (node (ref "U2") (pin "8") (pinfunction "VSSA_8") (pintype "passive"))
      (node (ref "U3") (pin "8") (pinfunction "COM_8") (pintype "passive"))
      (node (ref "U4") (pin "2") (pinfunction "GND_2") (pintype "passive"))
      (node (ref "U5") (pin "2") (pinfunction "GND_2") (pintype "passive"))
      (node (ref "U6") (pin "2") (pinfunction "GND_2") (pintype "passive"))
      (node (ref "U7") (pin "2") (pinfunction "GND_2") (pintype "passive"))
      (node (ref "U8") (pin "11") (pinfunction "GND_11") (pintype "passive"))
      (node (ref "X1") (pin "2") (pinfunction "VSS_2") (pintype "passive"))
    )
    (net (code "48") (name "Net-(D1-PadA)") (class "Default")
      (node (ref "D1") (pin "A") (pinfunction "A_A") (pintype "passive"))
      (node (ref "R2") (pin "1") (pinfunction "1_1") (pintype "passive"))
    )
    (net (code "49") (name "Net-(D2-PadA)") (class "Default")
      (node (ref "D2") (pin "A") (pinfunction "A_A") (pintype "passive"))
      (node (ref "R3") (pin "1") (pinfunction "1_1") (pintype "passive"))
    )
    (net (code "50") (name "Net-(D3-A)") (class "Default")
      (node (ref "D3") (pin "2") (pinfunction "A_2") (pintype "passive"))
      (node (ref "L3") (pin "2") (pinfunction "2_2") (pintype "passive"))
      (node (ref "U7") (pin "1") (pinfunction "SW_1") (pintype "passive"))
    )
    (net (code "51") (name "Net-(Q1-G)") (class "Default")
      (node (ref "Q1") (pin "4") (pinfunction "G_4") (pintype "passive"))
      (node (ref "R11") (pin "2") (pinfunction "2_2") (pintype "passive"))
    )
    (net (code "52") (name "Net-(Q2-G)") (class "Default")
      (node (ref "Q2") (pin "4") (pinfunction "G_4") (pintype "passive"))
      (node (ref "R12") (pin "2") (pinfunction "2_2") (pintype "passive"))
    )
    (net (code "53") (name "Net-(Q3-G)") (class "Default")
      (node (ref "Q3") (pin "4") (pinfunction "G_4") (pintype "passive"))
      (node (ref "R13") (pin "2") (pinfunction "2_2") (pintype "passive"))
    )
    (net (code "54") (name "Net-(Q4-G)") (class "Default")
      (node (ref "Q4") (pin "4") (pinfunction "G_4") (pintype "passive"))
      (node (ref "R14") (pin "2") (pinfunction "2_2") (pintype "passive"))
    )
    (net (code "55") (name "Net-(Q5-G)") (class "Default")
      (node (ref "Q5") (pin "4") (pinfunction "G_4") (pintype "passive"))
      (node (ref "R15") (pin "2") (pinfunction "2_2") (pintype "passive"))
    )
    (net (code "56") (name "Net-(Q6-G)") (class "Default")
      (node (ref "Q6") (pin "4") (pinfunction "G_4") (pintype "passive"))
      (node (ref "R16") (pin "2") (pinfunction "2_2") (pintype "passive"))
    )
    (net (code "57") (name "Net-(U5-BS)") (class "Default")
      (node (ref "C8") (pin "2") (pinfunction "2_2") (pintype "passive"))
      (node (ref "U5") (pin "1") (pinfunction "BS_1") (pintype "passive"))
    )
    (net (code "58") (name "Net-(U5-EN)") (class "Default")
      (node (ref "R6") (pin "1") (pinfunction "1_1") (pintype "passive"))
      (node (ref "U5") (pin "4") (pinfunction "EN_4") (pintype "passive"))
    )
    (net (code "59") (name "Net-(U5-FB)") (class "Default")
      (node (ref "R5") (pin "1") (pinfunction "1_1") (pintype "passive"))
      (node (ref "R7") (pin "2") (pinfunction "2_2") (pintype "passive"))
      (node (ref "U5") (pin "3") (pinfunction "FB_3") (pintype "passive"))
    )
    (net (code "60") (name "Net-(U5-SW)") (class "Default")
      (node (ref "C8") (pin "1") (pinfunction "1_1") (pintype "passive"))
      (node (ref "L2") (pin "1") (pinfunction "1_1") (pintype "passive"))
      (node (ref "U5") (pin "6") (pinfunction "SW_6") (pintype "passive"))
    )
    (net (code "61") (name "Net-(U7-EN)") (class "Default")
      (node (ref "R9") (pin "1") (pinfunction "1_1") (pintype "passive"))
      (node (ref "U7") (pin "4") (pinfunction "EN_4") (pintype "passive"))
    )
    (net (code "62") (name "Net-(U7-FB)") (class "Default")
      (node (ref "R10") (pin "2") (pinfunction "2_2") (pintype "passive"))
      (node (ref "R8") (pin "1") (pinfunction "1_1") (pintype "passive"))
      (node (ref "U7") (pin "3") (pinfunction "FB_3") (pintype "passive"))
    )
    (net (code "63") (name "Net-(U8A-IN1+)") (class "Default")
      (node (ref "C27") (pin "2") (pinfunction "2_2") (pintype "passive"))
      (node (ref "R22") (pin "1") (pinfunction "1_1") (pintype "passive"))
      (node (ref "R23") (pin "2") (pinfunction "2_2") (pintype "passive"))
      (node (ref "U8") (pin "3") (pinfunction "IN1+_3") (pintype "passive"))
    )
    (net (code "64") (name "Net-(U8B-IN2+)") (class "Default")
      (node (ref "R27") (pin "1") (pinfunction "1_1") (pintype "passive"))
      (node (ref "R29") (pin "2") (pinfunction "2_2") (pintype "passive"))
      (node (ref "U8") (pin "5") (pinfunction "IN2+_5") (pintype "passive"))
    )
    (net (code "65") (name "Net-(U8B-IN2-)") (class "Default")
      (node (ref "R31") (pin "2") (pinfunction "2_2") (pintype "passive"))
      (node (ref "R33") (pin "2") (pinfunction "2_2") (pintype "passive"))
      (node (ref "U8") (pin "6") (pinfunction "IN2-_6") (pintype "passive"))
    )
    (net (code "66") (name "Net-(U8C-IN3+)") (class "Default")
      (node (ref "R26") (pin "1") (pinfunction "1_1") (pintype "passive"))
      (node (ref "R28") (pin "2") (pinfunction "2_2") (pintype "passive"))
      (node (ref "U8") (pin "10") (pinfunction "IN3+_10") (pintype "passive"))
    )
    (net (code "67") (name "Net-(U8C-IN3-)") (class "Default")
      (node (ref "R30") (pin "2") (pinfunction "2_2") (pintype "passive"))
      (node (ref "R32") (pin "2") (pinfunction "2_2") (pintype "passive"))
      (node (ref "U8") (pin "9") (pinfunction "IN3-_9") (pintype "passive"))
    )
    (net (code "68") (name "Net-(U8D-IN4+)") (class "Default")
      (node (ref "R20") (pin "1") (pinfunction "1_1") (pintype "passive"))
      (node (ref "R21") (pin "2") (pinfunction "2_2") (pintype "passive"))
      (node (ref "U8") (pin "12") (pinfunction "IN4+_12") (pintype "passive"))
    )
    (net (code "69") (name "Net-(U8D-IN4-)") (class "Default")
      (node (ref "R24") (pin "2") (pinfunction "2_2") (pintype "passive"))
      (node (ref "R25") (pin "2") (pinfunction "2_2") (pintype "passive"))
      (node (ref "U8") (pin "13") (pinfunction "IN4-_13") (pintype "passive"))
    )
    (net (code "70") (name "PGND") (class "Default")
      (node (ref "R17") (pin "1") (pinfunction "1_1") (pintype "passive"))
      (node (ref "R18") (pin "1") (pinfunction "1_1") (pintype "passive"))
      (node (ref "R19") (pin "1") (pinfunction "1_1") (pintype "passive"))
    )
    (net (code "71") (name "VGS") (class "Default")
      (node (ref "C13") (pin "2") (pinfunction "2_2") (pintype "passive"))
      (node (ref "C14") (pin "2") (pinfunction "2_2") (pintype "passive"))
      (node (ref "C22") (pin "2") (pinfunction "2_2") (pintype "passive"))
      (node (ref "C25") (pin "2") (pinfunction "2_2") (pintype "passive"))
      (node (ref "D3") (pin "1") (pinfunction "K_1") (pintype "passive"))
      (node (ref "D4") (pin "2") (pinfunction "A_2") (pintype "passive"))
      (node (ref "D5") (pin "2") (pinfunction "A_2") (pintype "passive"))
      (node (ref "D6") (pin "2") (pinfunction "A_2") (pintype "passive"))
      (node (ref "R8") (pin "2") (pinfunction "2_2") (pintype "passive"))
      (node (ref "U3") (pin "7") (pinfunction "VCC_7") (pintype "passive"))
    )
    (net (code "72") (name "unconnected-(H1-1-Pad3)") (class "Default")
      (node (ref "H1") (pin "3") (pinfunction "1_3") (pintype "passive"))
    )
    (net (code "73") (name "unconnected-(H1-3-Pad1)") (class "Default")
      (node (ref "H1") (pin "1") (pinfunction "3_1") (pintype "passive"))
    )
    (net (code "74") (name "unconnected-(H1-Pad2)") (class "Default")
      (node (ref "H1") (pin "2") (pinfunction "2_2") (pintype "passive"))
    )
    (net (code "75") (name "unconnected-(U1-A-Pad16)") (class "Default")
      (node (ref "U1") (pin "16") (pinfunction "A_16") (pintype "passive"))
    )
    (net (code "76") (name "unconnected-(U1-B-Pad15)") (class "Default")
      (node (ref "U1") (pin "15") (pinfunction "B_15") (pintype "passive"))
    )
    (net (code "77") (name "unconnected-(U1-ERROR-Pad13)") (class "Default")
      (node (ref "U1") (pin "13") (pinfunction "ERROR_13") (pintype "passive"))
    )
    (net (code "78") (name "unconnected-(U1-OUT-Pad10)") (class "Default")
      (node (ref "U1") (pin "10") (pinfunction "OUT_10") (pintype "passive"))
    )
    (net (code "79") (name "unconnected-(U1-U-Pad1)") (class "Default")
      (node (ref "U1") (pin "1") (pinfunction "U_1") (pintype "passive"))
    )
    (net (code "80") (name "unconnected-(U1-V-Pad2)") (class "Default")
      (node (ref "U1") (pin "2") (pinfunction "V_2") (pintype "passive"))
    )
    (net (code "81") (name "unconnected-(U1-W-Pad3)") (class "Default")
      (node (ref "U1") (pin "3") (pinfunction "W_3") (pintype "passive"))
    )
    (net (code "82") (name "unconnected-(U1-Z-Pad14)") (class "Default")
      (node (ref "U1") (pin "14") (pinfunction "Z_14") (pintype "passive"))
    )
    (net (code "83") (name "unconnected-(U2-PB0-Pad18)") (class "Default")
      (node (ref "U2") (pin "18") (pinfunction "PB0_18") (pintype "passive"))
    )
    (net (code "84") (name "unconnected-(U2-PB1-Pad19)") (class "Default")
      (node (ref "U2") (pin "19") (pinfunction "PB1_19") (pintype "passive"))
    )
    (net (code "85") (name "unconnected-(U2-PB2-Pad20)") (class "Default")
      (node (ref "U2") (pin "20") (pinfunction "PB2_20") (pintype "passive"))
    )
    (net (code "86") (name "unconnected-(U2-PB3-Pad39)") (class "Default")
      (node (ref "U2") (pin "39") (pinfunction "PB3_39") (pintype "passive"))
    )
    (net (code "87") (name "unconnected-(U2-PB4-Pad40)") (class "Default")
      (node (ref "U2") (pin "40") (pinfunction "PB4_40") (pintype "passive"))
    )
    (net (code "88") (name "unconnected-(U2-PB5-Pad41)") (class "Default")
      (node (ref "U2") (pin "41") (pinfunction "PB5_41") (pintype "passive"))
    )
    (net (code "89") (name "unconnected-(U2-PB8-Pad45)") (class "Default")
      (node (ref "U2") (pin "45") (pinfunction "PB8_45") (pintype "passive"))
    )
    (net (code "90") (name "unconnected-(U2-PB9-Pad46)") (class "Default")
      (node (ref "U2") (pin "46") (pinfunction "PB9_46") (pintype "passive"))
    )
    (net (code "91") (name "unconnected-(U2-PB10-Pad21)") (class "Default")
      (node (ref "U2") (pin "21") (pinfunction "PB10_21") (pintype "passive"))
    )
    (net (code "92") (name "unconnected-(U2-PB11-Pad22)") (class "Default")
      (node (ref "U2") (pin "22") (pinfunction "PB11_22") (pintype "passive"))
    )
    (net (code "93") (name "unconnected-(U2-PB12-Pad25)") (class "Default")
      (node (ref "U2") (pin "25") (pinfunction "PB12_25") (pintype "passive"))
    )
    (net (code "94") (name "unconnected-(U2-PC14-OSC32IN-Pad3)") (class "Default")
      (node (ref "U2") (pin "3") (pinfunction "PC14-OSC32IN_3") (pintype "passive"))
    )
    (net (code "95") (name "unconnected-(U2-PC15-OSC32OUT-Pad4)") (class "Default")
      (node (ref "U2") (pin "4") (pinfunction "PC15-OSC32OUT_4") (pintype "passive"))
    )
    (net (code "96") (name "unconnected-(U4-N{slash}C-Pad4)") (class "Default")
      (node (ref "U4") (pin "4") (pinfunction "N/C_4") (pintype "passive"))
    )
    (net (code "97") (name "unconnected-(U6-N{slash}C-Pad4)") (class "Default")
      (node (ref "U6") (pin "4") (pinfunction "N/C_4") (pintype "passive"))
    )
    (net (code "98") (name "unconnected-(U7-NC-Pad6)") (class "Default")
      (node (ref "U7") (pin "6") (pinfunction "NC_6") (pintype "passive"))
    )
  )
)
